# design.net
KiCad netlist of a schematic drawn in Altium Designer
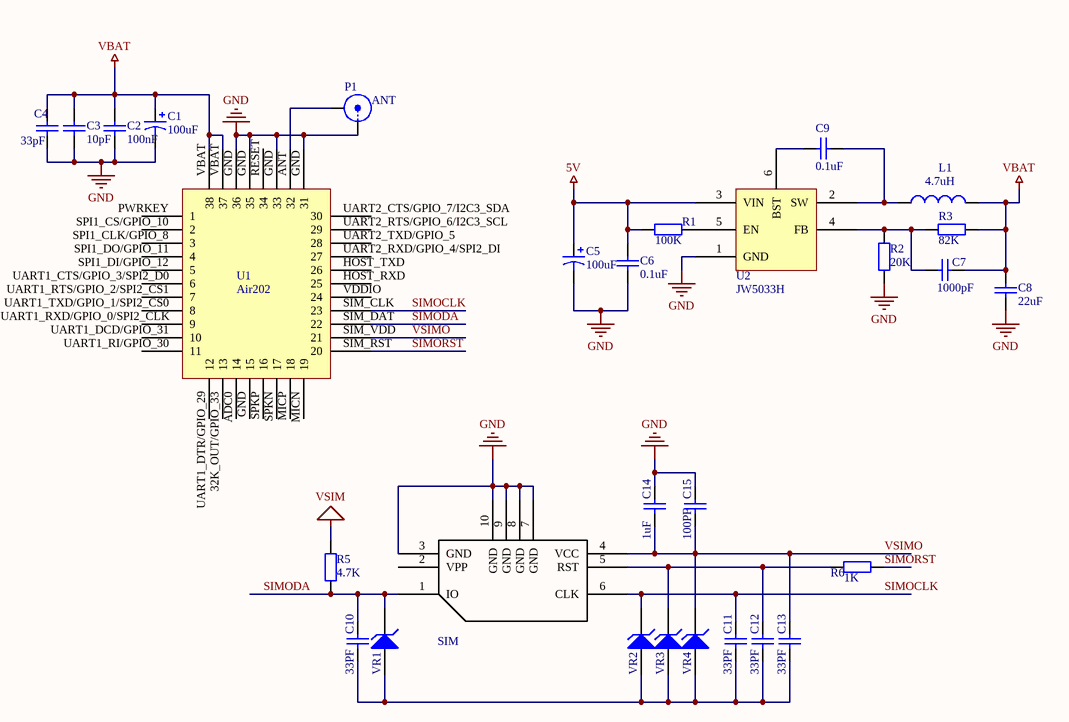
[diagram p0: 移动扫码模块.SchDoc]

(export (version "E")
  (design (tool "Eeschema 10.0.6"))
  (components
    (comp (ref "C1")
      (value "100uF")
      (footprint "RB7.6-15")
      (description "Polarized Capacitor (Radial)")
      (fields (field (name "Comment") "Cap Pol1") (field (name "PUBLISHER") "Altium Limited"))
      (libsource (lib "Miscellaneous Devices") (part "Cap Pol1"))
    )
    (comp (ref "C2")
      (value "100nF")
      (footprint "RAD-0.3")
      (description "Capacitor")
      (fields (field (name "Comment") "Cap") (field (name "PUBLISHER") "Altium Limited"))
      (libsource (lib "Miscellaneous Devices") (part "Cap"))
    )
    (comp (ref "C3")
      (value "10pF")
      (footprint "RAD-0.3")
      (description "Capacitor")
      (fields (field (name "Comment") "Cap") (field (name "PUBLISHER") "Altium Limited"))
      (libsource (lib "Miscellaneous Devices") (part "Cap"))
    )
    (comp (ref "C4")
      (value "33pF")
      (footprint "RAD-0.3")
      (description "Capacitor")
      (fields (field (name "Comment") "Cap") (field (name "PUBLISHER") "Altium Limited"))
      (libsource (lib "Miscellaneous Devices") (part "Cap"))
    )
    (comp (ref "C5")
      (value "100uF")
      (footprint "RB7.6-15")
      (description "Polarized Capacitor (Radial)")
      (fields (field (name "Comment") "Cap Pol1") (field (name "PUBLISHER") "Altium Limited"))
      (libsource (lib "Miscellaneous Devices") (part "Cap Pol1"))
    )
    (comp (ref "C6")
      (value "0.1uF")
      (footprint "RAD-0.3")
      (description "Capacitor")
      (fields (field (name "Comment") "Cap") (field (name "PUBLISHER") "Altium Limited"))
      (libsource (lib "Miscellaneous Devices") (part "Cap"))
    )
    (comp (ref "C7")
      (value "1000pF")
      (footprint "RAD-0.3")
      (description "Capacitor")
      (fields (field (name "Comment") "Cap") (field (name "PUBLISHER") "Altium Limited"))
      (libsource (lib "Miscellaneous Devices") (part "Cap"))
    )
    (comp (ref "C8")
      (value "22uF")
      (footprint "RAD-0.3")
      (description "Capacitor")
      (fields (field (name "Comment") "Cap") (field (name "PUBLISHER") "Altium Limited"))
      (libsource (lib "Miscellaneous Devices") (part "Cap"))
    )
    (comp (ref "C9")
      (value "0.1uF")
      (footprint "RAD-0.3")
      (description "Capacitor")
      (fields (field (name "Comment") "Cap") (field (name "PUBLISHER") "Altium Limited"))
      (libsource (lib "Miscellaneous Devices") (part "Cap"))
    )
    (comp (ref "C10")
      (value "33PF")
      (footprint "RAD-0.3")
      (description "Capacitor")
      (fields (field (name "Comment") "Cap") (field (name "PUBLISHER") "Altium Limited"))
      (libsource (lib "Miscellaneous Devices") (part "Cap"))
    )
    (comp (ref "C11")
      (value "33PF")
      (footprint "RAD-0.3")
      (description "Capacitor")
      (fields (field (name "Comment") "Cap") (field (name "PUBLISHER") "Altium Limited"))
      (libsource (lib "Miscellaneous Devices") (part "Cap"))
    )
    (comp (ref "C12")
      (value "33PF")
      (footprint "RAD-0.3")
      (description "Capacitor")
      (fields (field (name "Comment") "Cap") (field (name "PUBLISHER") "Altium Limited"))
      (libsource (lib "Miscellaneous Devices") (part "Cap"))
    )
    (comp (ref "C13")
      (value "33PF")
      (footprint "RAD-0.3")
      (description "Capacitor")
      (fields (field (name "Comment") "Cap") (field (name "PUBLISHER") "Altium Limited"))
      (libsource (lib "Miscellaneous Devices") (part "Cap"))
    )
    (comp (ref "C14")
      (value "1uF")
      (footprint "RAD-0.3")
      (description "Capacitor")
      (fields (field (name "Comment") "Cap") (field (name "PUBLISHER") "Altium Limited"))
      (libsource (lib "Miscellaneous Devices") (part "Cap"))
    )
    (comp (ref "C15")
      (value "100PF")
      (footprint "RAD-0.3")
      (description "Capacitor")
      (fields (field (name "Comment") "Cap") (field (name "PUBLISHER") "Altium Limited"))
      (libsource (lib "Miscellaneous Devices") (part "Cap"))
    )
    (comp (ref "L1")
      (value "4.7uH")
      (footprint "0402-A")
      (description "Inductor")
      (fields (field (name "PUBLISHER") "Altium Limited"))
      (libsource (lib "Miscellaneous Devices") (part "Inductor"))
    )
    (comp (ref "P1")
      (value "ANT")
      (footprint "BNC_RA CON")
      (description "BNC Elbow Connector")
      (fields (field (name "PUBLISHER") "Altium Limited"))
      (libsource (lib "Miscellaneous Connectors") (part "BNC"))
    )
    (comp (ref "R1")
      (value "100K")
      (footprint "AXIAL-0.4")
      (description "Resistor")
      (fields (field (name "Comment") "Res2") (field (name "PUBLISHER") "Altium Limited"))
      (libsource (lib "") (part "Res2_1"))
    )
    (comp (ref "R2")
      (value "20K")
      (footprint "AXIAL-0.4")
      (description "Resistor")
      (fields (field (name "Comment") "Res2") (field (name "PUBLISHER") "Altium Limited"))
      (libsource (lib "") (part "Res2_3"))
    )
    (comp (ref "R3")
      (value "82K")
      (footprint "AXIAL-0.4")
      (description "Resistor")
      (fields (field (name "Comment") "Res2") (field (name "PUBLISHER") "Altium Limited"))
      (libsource (lib "") (part "Res2_1"))
    )
    (comp (ref "R5")
      (value "4.7K")
      (footprint "AXIAL-0.4")
      (description "Resistor")
      (fields (field (name "Comment") "Res2") (field (name "PUBLISHER") "Altium Limited"))
      (libsource (lib "Miscellaneous Devices") (part "Res2"))
    )
    (comp (ref "R6")
      (value "1K")
      (footprint "AXIAL-0.4")
      (description "Resistor")
      (fields (field (name "Comment") "Res2") (field (name "PUBLISHER") "Altium Limited"))
      (libsource (lib "") (part "Res2_2"))
    )
    (comp (ref "SIM") (value "NB") (libsource (lib "Schlib1") (part "NB")))
    (comp (ref "U1") (value "Air202") (libsource (lib "Schlib1") (part "Component_1")))
    (comp (ref "U2") (value "JW5033H") (libsource (lib "Schlib1") (part "JW5033H")))
    (comp (ref "VR1")
      (value "D Zener")
      (footprint "DIODE-0.7")
      (description "Zener Diode")
      (fields (field (name "PUBLISHER") "Altium Limited"))
      (libsource (lib "Miscellaneous Devices") (part "D Zener"))
    )
    (comp (ref "VR2")
      (value "D Zener")
      (footprint "DIODE-0.7")
      (description "Zener Diode")
      (fields (field (name "PUBLISHER") "Altium Limited"))
      (libsource (lib "Miscellaneous Devices") (part "D Zener"))
    )
    (comp (ref "VR3")
      (value "D Zener")
      (footprint "DIODE-0.7")
      (description "Zener Diode")
      (fields (field (name "PUBLISHER") "Altium Limited"))
      (libsource (lib "Miscellaneous Devices") (part "D Zener"))
    )
    (comp (ref "VR4")
      (value "D Zener")
      (footprint "DIODE-0.7")
      (description "Zener Diode")
      (fields (field (name "PUBLISHER") "Altium Limited"))
      (libsource (lib "Miscellaneous Devices") (part "D Zener"))
    )
  )
  (nets
    (net (code "1") (name "/SIMOCLK") (class "Default")
      (node (ref "C11") (pin "2") (pinfunction "2_2") (pintype "passive"))
      (node (ref "SIM") (pin "6") (pinfunction "CLK_6") (pintype "passive"))
      (node (ref "U1") (pin "SIM_CLK") (pinfunction "23_SIM_CLK") (pintype "passive"))
      (node (ref "VR2") (pin "2") (pinfunction "K_2") (pintype "passive"))
    )
    (net (code "2") (name "/SIMODA") (class "Default")
      (node (ref "C10") (pin "2") (pinfunction "2_2") (pintype "passive"))
      (node (ref "R5") (pin "1") (pinfunction "1_1") (pintype "passive"))
      (node (ref "SIM") (pin "1") (pinfunction "IO_1") (pintype "passive"))
      (node (ref "U1") (pin "SIM_DAT") (pinfunction "22_SIM_DAT") (pintype "passive"))
      (node (ref "VR1") (pin "2") (pinfunction "K_2") (pintype "passive"))
    )
    (net (code "3") (name "/SIMORST") (class "Default")
      (node (ref "R6") (pin "1") (pinfunction "1_1") (pintype "passive"))
      (node (ref "U1") (pin "SIM_RST") (pinfunction "20_SIM_RST") (pintype "passive"))
    )
    (net (code "4") (name "/VSIMO") (class "Default")
      (node (ref "C13") (pin "2") (pinfunction "2_2") (pintype "passive"))
      (node (ref "C14") (pin "1") (pinfunction "1_1") (pintype "passive"))
      (node (ref "C15") (pin "1") (pinfunction "1_1") (pintype "passive"))
      (node (ref "SIM") (pin "4") (pinfunction "VCC_4") (pintype "passive"))
      (node (ref "U1") (pin "SIM_VDD") (pinfunction "21_SIM_VDD") (pintype "passive"))
      (node (ref "VR4") (pin "2") (pinfunction "K_2") (pintype "passive"))
    )
    (net (code "5") (name "5V") (class "Default")
      (node (ref "C5") (pin "1") (pinfunction "1_1") (pintype "passive"))
      (node (ref "C6") (pin "2") (pinfunction "2_2") (pintype "passive"))
      (node (ref "R1") (pin "1") (pinfunction "1_1") (pintype "passive"))
      (node (ref "U2") (pin "3") (pinfunction "VIN_3") (pintype "passive"))
    )
    (net (code "6") (name "GND") (class "Default")
      (node (ref "C1") (pin "2") (pinfunction "2_2") (pintype "passive"))
      (node (ref "C14") (pin "2") (pinfunction "2_2") (pintype "passive"))
      (node (ref "C15") (pin "2") (pinfunction "2_2") (pintype "passive"))
      (node (ref "C2") (pin "1") (pinfunction "1_1") (pintype "passive"))
      (node (ref "C3") (pin "1") (pinfunction "1_1") (pintype "passive"))
      (node (ref "C4") (pin "1") (pinfunction "1_1") (pintype "passive"))
      (node (ref "C5") (pin "2") (pinfunction "2_2") (pintype "passive"))
      (node (ref "C6") (pin "1") (pinfunction "1_1") (pintype "passive"))
      (node (ref "C8") (pin "2") (pinfunction "2_2") (pintype "passive"))
      (node (ref "P1") (pin "1") (pinfunction "X_1") (pintype "passive"))
      (node (ref "R2") (pin "2") (pinfunction "2_2") (pintype "passive"))
      (node (ref "SIM") (pin "10") (pinfunction "GND_10") (pintype "passive"))
      (node (ref "SIM") (pin "3") (pinfunction "GND_3") (pintype "passive"))
      (node (ref "SIM") (pin "7") (pinfunction "GND_7") (pintype "passive"))
      (node (ref "SIM") (pin "8") (pinfunction "GND_8") (pintype "passive"))
      (node (ref "SIM") (pin "9") (pinfunction "GND_9") (pintype "passive"))
      (node (ref "U1") (pin "GND") (pinfunction "36_GND") (pintype "passive"))
      (node (ref "U2") (pin "1") (pinfunction "GND_1") (pintype "passive"))
    )
    (net (code "7") (name "Net-(P1-Y)") (class "Default")
      (node (ref "P1") (pin "2") (pinfunction "Y_2") (pintype "passive"))
      (node (ref "U1") (pin "ANT") (pinfunction "32_ANT") (pintype "passive"))
    )
    (net (code "8") (name "Net-(SIM-RST)") (class "Default")
      (node (ref "C12") (pin "2") (pinfunction "2_2") (pintype "passive"))
      (node (ref "R6") (pin "2") (pinfunction "2_2") (pintype "passive"))
      (node (ref "SIM") (pin "5") (pinfunction "RST_5") (pintype "passive"))
      (node (ref "VR3") (pin "2") (pinfunction "K_2") (pintype "passive"))
    )
    (net (code "9") (name "Net-(U2-BST)") (class "Default")
      (node (ref "C9") (pin "1") (pinfunction "1_1") (pintype "passive"))
      (node (ref "U2") (pin "6") (pinfunction "BST_6") (pintype "passive"))
    )
    (net (code "10") (name "Net-(U2-EN)") (class "Default")
      (node (ref "R1") (pin "2") (pinfunction "2_2") (pintype "passive"))
      (node (ref "U2") (pin "5") (pinfunction "EN_5") (pintype "passive"))
    )
    (net (code "11") (name "Net-(U2-FB)") (class "Default")
      (node (ref "C7") (pin "2") (pinfunction "2_2") (pintype "passive"))
      (node (ref "R2") (pin "1") (pinfunction "1_1") (pintype "passive"))
      (node (ref "R3") (pin "1") (pinfunction "1_1") (pintype "passive"))
      (node (ref "U2") (pin "4") (pinfunction "FB_4") (pintype "passive"))
    )
    (net (code "12") (name "Net-(U2-SW)") (class "Default")
      (node (ref "C9") (pin "2") (pinfunction "2_2") (pintype "passive"))
      (node (ref "L1") (pin "1") (pinfunction "1_1") (pintype "passive"))
      (node (ref "U2") (pin "2") (pinfunction "SW_2") (pintype "passive"))
    )
    (net (code "13") (name "Net-(VR1-A)") (class "Default")
      (node (ref "C10") (pin "1") (pinfunction "1_1") (pintype "passive"))
      (node (ref "C11") (pin "1") (pinfunction "1_1") (pintype "passive"))
      (node (ref "C12") (pin "1") (pinfunction "1_1") (pintype "passive"))
      (node (ref "C13") (pin "1") (pinfunction "1_1") (pintype "passive"))
      (node (ref "VR1") (pin "1") (pinfunction "A_1") (pintype "passive"))
      (node (ref "VR2") (pin "1") (pinfunction "A_1") (pintype "passive"))
      (node (ref "VR3") (pin "1") (pinfunction "A_1") (pintype "passive"))
      (node (ref "VR4") (pin "1") (pinfunction "A_1") (pintype "passive"))
    )
    (net (code "14") (name "VBAT") (class "Default")
      (node (ref "C1") (pin "1") (pinfunction "1_1") (pintype "passive"))
      (node (ref "C2") (pin "2") (pinfunction "2_2") (pintype "passive"))
      (node (ref "C3") (pin "2") (pinfunction "2_2") (pintype "passive"))
      (node (ref "C4") (pin "2") (pinfunction "2_2") (pintype "passive"))
      (node (ref "C7") (pin "1") (pinfunction "1_1") (pintype "passive"))
      (node (ref "C8") (pin "1") (pinfunction "1_1") (pintype "passive"))
      (node (ref "L1") (pin "2") (pinfunction "2_2") (pintype "passive"))
      (node (ref "R3") (pin "2") (pinfunction "2_2") (pintype "passive"))
      (node (ref "U1") (pin "VBAT") (pinfunction "38_VBAT") (pintype "passive"))
    )
    (net (code "15") (name "VSIM") (class "Default")
      (node (ref "R5") (pin "2") (pinfunction "2_2") (pintype "passive"))
    )
    (net (code "16") (name "unconnected-(SIM-VPP-Pad2)") (class "Default")
      (node (ref "SIM") (pin "2") (pinfunction "VPP_2") (pintype "passive"))
    )
    (net (code "17") (name "unconnected-(U1-1-PadPWRKEY)") (class "Default")
      (node (ref "U1") (pin "PWRKEY") (pinfunction "1_PWRKEY") (pintype "passive"))
    )
    (net (code "18") (name "unconnected-(U1-2-PadSPI1_CS{slash}GPIO_10)") (class "Default")
      (node (ref "U1") (pin "SPI1_CS/GPIO_10") (pinfunction "2_SPI1_CS/GPIO_10") (pintype "passive"))
    )
    (net (code "19") (name "unconnected-(U1-3-PadSPI1_CLK{slash}GPIO_8)") (class "Default")
      (node (ref "U1") (pin "SPI1_CLK/GPIO_8") (pinfunction "3_SPI1_CLK/GPIO_8") (pintype "passive"))
    )
    (net (code "20") (name "unconnected-(U1-4-PadSPI1_DO{slash}GPIO_11)") (class "Default")
      (node (ref "U1") (pin "SPI1_DO/GPIO_11") (pinfunction "4_SPI1_DO/GPIO_11") (pintype "passive"))
    )
    (net (code "21") (name "unconnected-(U1-5-PadSPI1_DI{slash}GPIO_12)") (class "Default")
      (node (ref "U1") (pin "SPI1_DI/GPIO_12") (pinfunction "5_SPI1_DI/GPIO_12") (pintype "passive"))
    )
    (net (code "22") (name "unconnected-(U1-6-PadUART1_CTS{slash}GPIO_3{slash}SPI2_D0)") (class "Default")
      (node (ref "U1") (pin "UART1_CTS/GPIO_3/SPI2_D0") (pinfunction "6_UART1_CTS/GPIO_3/SPI2_D0") (pintype "passive"))
    )
    (net (code "23") (name "unconnected-(U1-7-PadUART1_RTS{slash}GPIO_2{slash}SPI2_CS1)") (class "Default")
      (node (ref "U1") (pin "UART1_RTS/GPIO_2/SPI2_CS1") (pinfunction "7_UART1_RTS/GPIO_2/SPI2_CS1") (pintype "passive"))
    )
    (net (code "24") (name "unconnected-(U1-8-PadUART1_TXD{slash}GPIO_1{slash}SPI2_CS0)") (class "Default")
      (node (ref "U1") (pin "UART1_TXD/GPIO_1/SPI2_CS0") (pinfunction "8_UART1_TXD/GPIO_1/SPI2_CS0") (pintype "passive"))
    )
    (net (code "25") (name "unconnected-(U1-9-PadUART1_RXD{slash}GPIO_0{slash}SPI2_CLK)") (class "Default")
      (node (ref "U1") (pin "UART1_RXD/GPIO_0/SPI2_CLK") (pinfunction "9_UART1_RXD/GPIO_0/SPI2_CLK") (pintype "passive"))
    )
    (net (code "26") (name "unconnected-(U1-10-PadUART1_DCD{slash}GPIO_31)") (class "Default")
      (node (ref "U1") (pin "UART1_DCD/GPIO_31") (pinfunction "10_UART1_DCD/GPIO_31") (pintype "passive"))
    )
    (net (code "27") (name "unconnected-(U1-11-PadUART1_RI{slash}GPIO_30)") (class "Default")
      (node (ref "U1") (pin "UART1_RI/GPIO_30") (pinfunction "11_UART1_RI/GPIO_30") (pintype "passive"))
    )
    (net (code "28") (name "unconnected-(U1-12-PadUART1_DTR{slash}GPIO_29)") (class "Default")
      (node (ref "U1") (pin "UART1_DTR/GPIO_29") (pinfunction "12_UART1_DTR/GPIO_29") (pintype "passive"))
    )
    (net (code "29") (name "unconnected-(U1-13-Pad32K_OUT{slash}GPIO_33)") (class "Default")
      (node (ref "U1") (pin "32K_OUT/GPIO_33") (pinfunction "13_32K_OUT/GPIO_33") (pintype "passive"))
    )
    (net (code "30") (name "unconnected-(U1-14-PadADC0)") (class "Default")
      (node (ref "U1") (pin "ADC0") (pinfunction "14_ADC0") (pintype "passive"))
    )
    (net (code "31") (name "unconnected-(U1-15-PadGND)") (class "Default")
      (node (ref "U1") (pin "GND") (pinfunction "15_GND") (pintype "passive"))
    )
    (net (code "32") (name "unconnected-(U1-16-PadSPKP)") (class "Default")
      (node (ref "U1") (pin "SPKP") (pinfunction "16_SPKP") (pintype "passive"))
    )
    (net (code "33") (name "unconnected-(U1-17-PadSPKN)") (class "Default")
      (node (ref "U1") (pin "SPKN") (pinfunction "17_SPKN") (pintype "passive"))
    )
    (net (code "34") (name "unconnected-(U1-18-PadMICP)") (class "Default")
      (node (ref "U1") (pin "MICP") (pinfunction "18_MICP") (pintype "passive"))
    )
    (net (code "35") (name "unconnected-(U1-19-PadMICN)") (class "Default")
      (node (ref "U1") (pin "MICN") (pinfunction "19_MICN") (pintype "passive"))
    )
    (net (code "36") (name "unconnected-(U1-24-PadVDDIO)") (class "Default")
      (node (ref "U1") (pin "VDDIO") (pinfunction "24_VDDIO") (pintype "passive"))
    )
    (net (code "37") (name "unconnected-(U1-25-PadHOST_RXD)") (class "Default")
      (node (ref "U1") (pin "HOST_RXD") (pinfunction "25_HOST_RXD") (pintype "passive"))
    )
    (net (code "38") (name "unconnected-(U1-26-PadHOST_TXD)") (class "Default")
      (node (ref "U1") (pin "HOST_TXD") (pinfunction "26_HOST_TXD") (pintype "passive"))
    )
    (net (code "39") (name "unconnected-(U1-27-PadUART2_RXD{slash}GPIO_4{slash}SPI2_DI)") (class "Default")
      (node (ref "U1") (pin "UART2_RXD/GPIO_4/SPI2_DI") (pinfunction "27_UART2_RXD/GPIO_4/SPI2_DI") (pintype "passive"))
    )
    (net (code "40") (name "unconnected-(U1-28-PadUART2_TXD{slash}GPIO_5)") (class "Default")
      (node (ref "U1") (pin "UART2_TXD/GPIO_5") (pinfunction "28_UART2_TXD/GPIO_5") (pintype "passive"))
    )
    (net (code "41") (name "unconnected-(U1-29-PadUART2_RTS{slash}GPIO_6{slash}I2C3_SCL)") (class "Default")
      (node (ref "U1") (pin "UART2_RTS/GPIO_6/I2C3_SCL") (pinfunction "29_UART2_RTS/GPIO_6/I2C3_SCL") (pintype "passive"))
    )
    (net (code "42") (name "unconnected-(U1-30-PadUART2_CTS{slash}GPIO_7{slash}I2C3_SDA)") (class "Default")
      (node (ref "U1") (pin "UART2_CTS/GPIO_7/I2C3_SDA") (pinfunction "30_UART2_CTS/GPIO_7/I2C3_SDA") (pintype "passive"))
    )
    (net (code "43") (name "unconnected-(U1-34-PadRESET)") (class "Default")
      (node (ref "U1") (pin "RESET") (pinfunction "34_RESET") (pintype "passive"))
    )
  )
)
